# MCU.net
KiCad netlist of a schematic drawn in Altium Designer
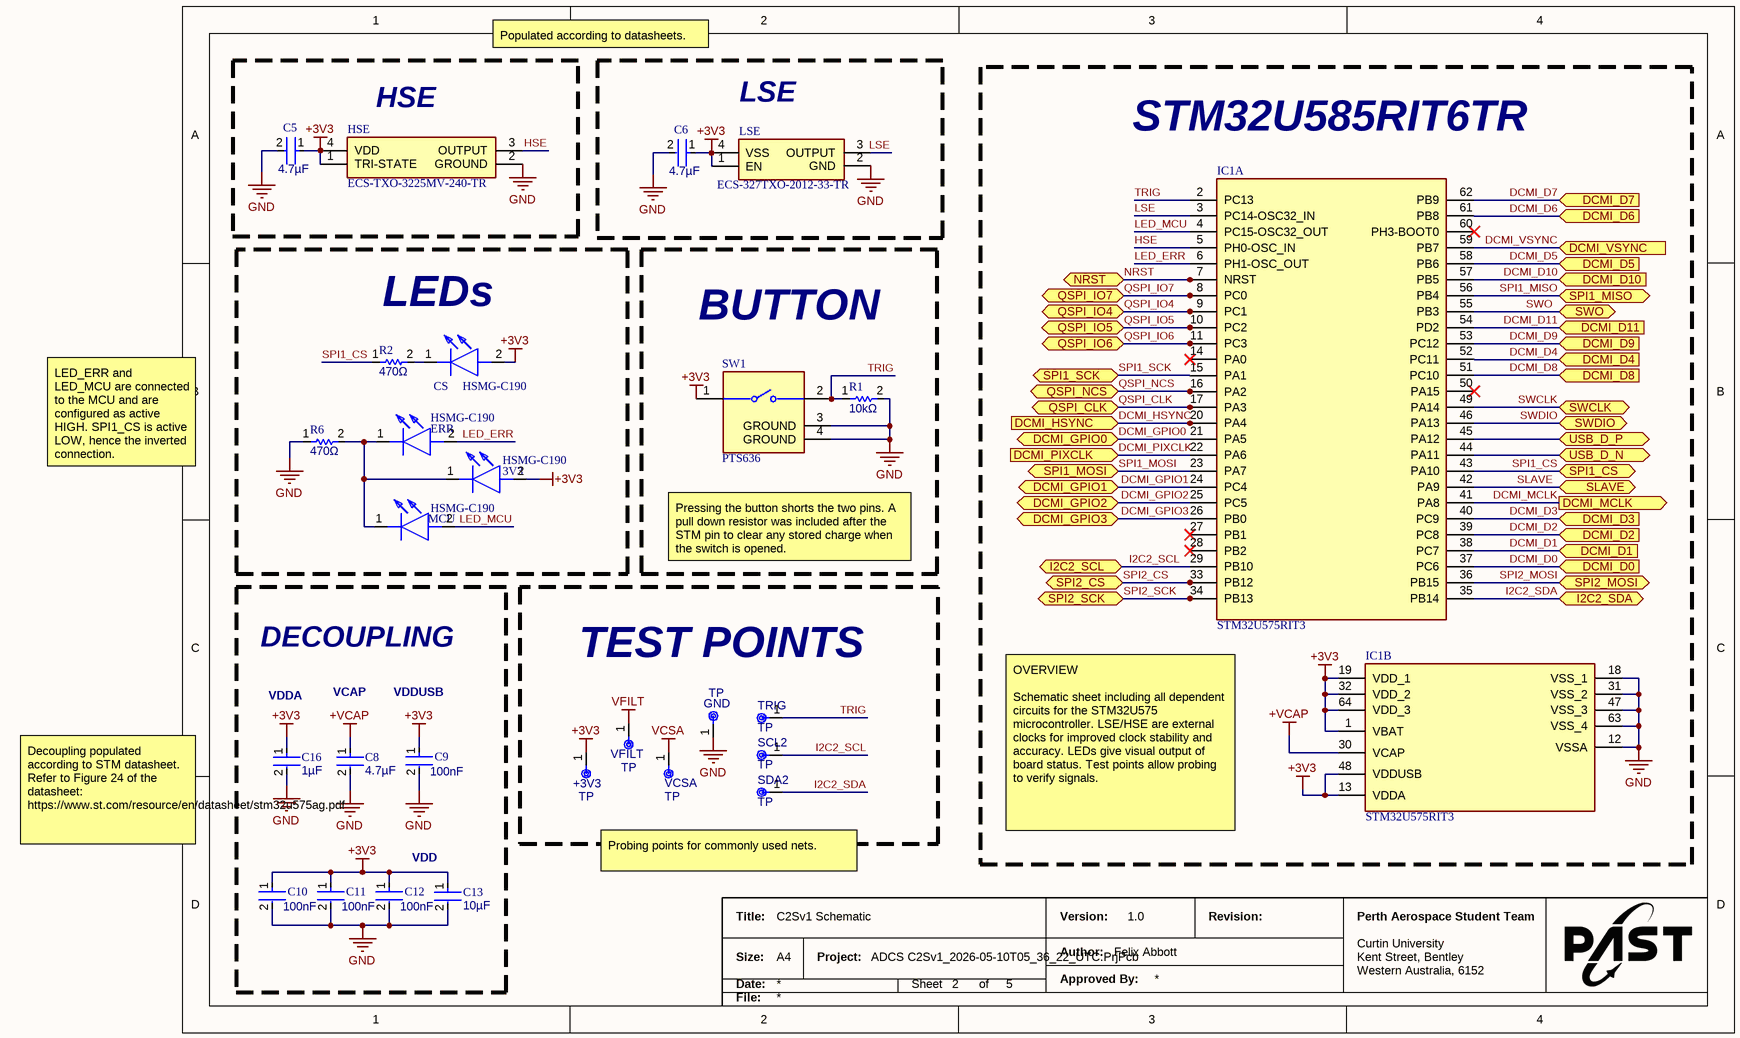
[diagram p0: MCU.SchDoc]

(export (version "E")
  (design (tool "Eeschema 10.0.6"))
  (components
    (comp (ref "+3V3")
      (value "TP")
      (footprint "TP06R")
      (description "test point")
      (fields (field (name "AUTHOR") "Raphael Ho"))
      (libsource (lib "Perth Aerospace Student Team") (part "CMP-001-0001-4"))
    )
    (comp (ref "3V3")
      (value "HSMG-C190")
      (footprint "LEDC1608X90N")
      (description "LED")
      (fields (field (name "MOUSER PART NUMBER") "630-HSMG-C190"))
      (libsource (lib "Perth Aerospace Student Team") (part "HSMG-C190"))
    )
    (comp (ref "C5")
      (value "4.7µF")
      (footprint "FP-GRT188-0_2-IPC_B")
      (fields
        (field (name "TOLERANCE") "10%")
        (field (name "Comment") "GRT188C81E475KE13J")
        (field (name "ADDED BY") "Felix")
      )
      (libsource (lib "Perth Aerospace Student Team") (part "02cd4be3c70576c341d710602a673aa"))
    )
    (comp (ref "C6")
      (value "4.7µF")
      (footprint "FP-GRT188-0_2-IPC_B")
      (fields
        (field (name "TOLERANCE") "10%")
        (field (name "Comment") "GRT188C81E475KE13J")
        (field (name "ADDED BY") "Felix")
      )
      (libsource (lib "Perth Aerospace Student Team") (part "02cd4be3c70576c341d710602a673aa"))
    )
    (comp (ref "C8")
      (value "4.7µF")
      (footprint "FP-GRT188-0_2-IPC_B")
      (fields
        (field (name "TOLERANCE") "10%")
        (field (name "Comment") "GRT188C81E475KE13J")
        (field (name "ADDED BY") "Felix")
      )
      (libsource (lib "Perth Aerospace Student Team") (part "02cd4be3c70576c341d710602a673aa"))
    )
    (comp (ref "C9")
      (value "100nF")
      (footprint "FP-GCM188-0_1-IPC_B")
      (description "Cap Ceramic 0.1uF 50V X8L 20% Pad SMD 0603 150C Automotive T/R")
      (fields
        (field (name "TOLERANCE") "20%")
        (field (name "Comment") "GCM188L81H104MA57D")
        (field (name "ADDED BY") "Felix")
      )
      (libsource (lib "Perth Aerospace Student Team") (part "02cd4be3c70576c341d710602a673aa"))
    )
    (comp (ref "C10")
      (value "100nF")
      (footprint "FP-GCM188-0_1-IPC_B")
      (description "Cap Ceramic 0.1uF 50V X8L 20% Pad SMD 0603 150C Automotive T/R")
      (fields
        (field (name "TOLERANCE") "20%")
        (field (name "Comment") "GCM188L81H104MA57D")
        (field (name "ADDED BY") "Felix")
      )
      (libsource (lib "Perth Aerospace Student Team") (part "02cd4be3c70576c341d710602a673aa"))
    )
    (comp (ref "C11")
      (value "100nF")
      (footprint "FP-GCM188-0_1-IPC_B")
      (description "Cap Ceramic 0.1uF 50V X8L 20% Pad SMD 0603 150C Automotive T/R")
      (fields
        (field (name "TOLERANCE") "20%")
        (field (name "Comment") "GCM188L81H104MA57D")
        (field (name "ADDED BY") "Felix")
      )
      (libsource (lib "Perth Aerospace Student Team") (part "02cd4be3c70576c341d710602a673aa"))
    )
    (comp (ref "C12")
      (value "100nF")
      (footprint "FP-GCM188-0_1-IPC_B")
      (description "Cap Ceramic 0.1uF 50V X8L 20% Pad SMD 0603 150C Automotive T/R")
      (fields
        (field (name "TOLERANCE") "20%")
        (field (name "Comment") "GCM188L81H104MA57D")
        (field (name "ADDED BY") "Felix")
      )
      (libsource (lib "Perth Aerospace Student Team") (part "02cd4be3c70576c341d710602a673aa"))
    )
    (comp (ref "C13")
      (value "10µF")
      (footprint "FP-GCM188-0_2-IPC_B")
      (description "6.3V 10uF X7T ±20% 0603 Multilayer Ceramic Capacitors MLCC - SMD/SMT ROHS")
      (fields
        (field (name "TOLERANCE") "20%")
        (field (name "Comment") "GCM188D70J106ME36D")
        (field (name "ADDED BY") "Felix")
      )
      (libsource (lib "Perth Aerospace Student Team") (part "11868f565c42a9108669ba33697ecf6"))
    )
    (comp (ref "C16")
      (value "1µF")
      (footprint "FP-GCM188-0_1-IPC_B")
      (description "16V 1uF X7R ±10% 0603 Multilayer Ceramic Capacitors MLCC - SMD/SMT ROHS")
      (fields
        (field (name "TOLERANCE") "10%")
        (field (name "Comment") "GCM188R71C105KA64J")
        (field (name "ADDED BY") "Felix")
      )
      (libsource (lib "Perth Aerospace Student Team") (part "02cd4be3c70576c341d710602a673aa"))
    )
    (comp (ref "CS")
      (value "HSMG-C190")
      (footprint "LEDC1608X90N")
      (description "LED")
      (fields (field (name "MOUSER PART NUMBER") "630-HSMG-C190"))
      (libsource (lib "Perth Aerospace Student Team") (part "HSMG-C190"))
    )
    (comp (ref "ERR")
      (value "HSMG-C190")
      (footprint "LEDC1608X90N")
      (description "LED")
      (fields (field (name "MOUSER PART NUMBER") "630-HSMG-C190"))
      (libsource (lib "Perth Aerospace Student Team") (part "HSMG-C190"))
    )
    (comp (ref "GND")
      (value "TP")
      (footprint "TP06R")
      (description "test point")
      (fields (field (name "AUTHOR") "Raphael Ho"))
      (libsource (lib "Perth Aerospace Student Team") (part "CMP-001-0001-4"))
    )
    (comp (ref "HSE")
      (value "ECS-TXO-3225MV-240-TR")
      (footprint "ECSTXO3225MV240TR")
      (description "Crystal or Oscillator")
      (fields (field (name "MOUSER PART NUMBER") "520-TXO-3225MV-240-T") (field (name "IMPORTED BY") "Felix"))
      (libsource (lib "Perth Aerospace Student Team") (part "ECS-TXO-3225MV-240-TR"))
    )
    (comp (ref "IC1")
      (value "STM32U575RIT3")
      (footprint "QFP50P1200X1200X160-64N")
      (description "Ultra-low-power Arm Cortex-M33 32-bit MCU+TrustZone+FPU")
      (fields (field (name "ADDED BY") "Felix Abbott"))
      (libsource (lib "Perth Aerospace Student Team") (part "STM32U575RIT3"))
    )
    (comp (ref "LSE")
      (value "ECS-327TXO-2012-33-TR")
      (footprint "ECS327TXO201233TR")
      (description "Crystal or Oscillator")
      (fields (field (name "MOUSER PART NUMBER") "520-327TXO-2012-33TR") (field (name "ADDED BY") "Felix"))
      (libsource (lib "Perth Aerospace Student Team") (part "ECS-327TXO-2012-33-TR"))
    )
    (comp (ref "MCU")
      (value "HSMG-C190")
      (footprint "LEDC1608X90N")
      (description "LED")
      (fields (field (name "MOUSER PART NUMBER") "630-HSMG-C190"))
      (libsource (lib "Perth Aerospace Student Team") (part "HSMG-C190"))
    )
    (comp (ref "R1")
      (value "10kΩ")
      (footprint "FP-CRCW0603-e3-IPC_C")
      (description "Resistor")
      (fields
        (field (name "TOLERANCE") "1%")
        (field (name "Comment") "CRCW060310K0FKED")
        (field (name "ADDED BY") "Felix")
      )
      (libsource (lib "") (part "1029c3af85768c4190bb7ad29bc67b5_1"))
    )
    (comp (ref "R2")
      (value "470Ω")
      (footprint "FP-CRCW0603-e3-IPC_C")
      (description "Resistor")
      (fields
        (field (name "TOLERANCE") "1%")
        (field (name "Comment") "CRCW0603470RFKEC")
        (field (name "ADDED BY") "Felix")
      )
      (libsource (lib "Perth Aerospace Student Team") (part "1029c3af85768c4190bb7ad29bc67b5"))
    )
    (comp (ref "R6")
      (value "470Ω")
      (footprint "FP-CRCW0603-e3-IPC_C")
      (description "Resistor")
      (fields
        (field (name "TOLERANCE") "1%")
        (field (name "Comment") "CRCW0603470RFKEC")
        (field (name "ADDED BY") "Felix")
      )
      (libsource (lib "Perth Aerospace Student Team") (part "1029c3af85768c4190bb7ad29bc67b5"))
    )
    (comp (ref "SCL2")
      (value "TP")
      (footprint "TP06R")
      (description "test point")
      (fields (field (name "AUTHOR") "Raphael Ho"))
      (libsource (lib "Perth Aerospace Student Team") (part "CMP-001-0001-4"))
    )
    (comp (ref "SDA2")
      (value "TP")
      (footprint "TP06R")
      (description "test point")
      (fields (field (name "AUTHOR") "Raphael Ho"))
      (libsource (lib "Perth Aerospace Student Team") (part "CMP-001-0001-4"))
    )
    (comp (ref "SW1")
      (value "PTS636")
      (footprint "FP-PTS636_SKG25_SMTR_LFS-MFG")
      (description "Tactile Switch")
      (fields (field (name "ADDED BY") "Felix A"))
      (libsource (lib "Perth Aerospace Student Team") (part "bdfe703aeb3461bf7c331fe9d798369"))
    )
    (comp (ref "TRIG")
      (value "TP")
      (footprint "TP06R")
      (description "test point")
      (fields (field (name "AUTHOR") "Raphael Ho"))
      (libsource (lib "Perth Aerospace Student Team") (part "CMP-001-0001-4"))
    )
    (comp (ref "VCSA")
      (value "TP")
      (footprint "TP06R")
      (description "test point")
      (fields (field (name "AUTHOR") "Raphael Ho"))
      (libsource (lib "Perth Aerospace Student Team") (part "CMP-001-0001-4"))
    )
    (comp (ref "VFILT")
      (value "TP")
      (footprint "TP06R")
      (description "test point")
      (fields (field (name "AUTHOR") "Raphael Ho"))
      (libsource (lib "Perth Aerospace Student Team") (part "CMP-001-0001-4"))
    )
  )
  (nets
    (net (code "1") (name "+3V3") (class "Default")
      (node (ref "+3V3") (pin "1") (pinfunction "TP_1") (pintype "passive"))
      (node (ref "3V3") (pin "2") (pinfunction "A_2") (pintype "passive"))
      (node (ref "C10") (pin "1") (pinfunction "1_1") (pintype "passive"))
      (node (ref "C11") (pin "1") (pinfunction "1_1") (pintype "passive"))
      (node (ref "C12") (pin "1") (pinfunction "1_1") (pintype "passive"))
      (node (ref "C13") (pin "1") (pinfunction "1_1") (pintype "passive"))
      (node (ref "C16") (pin "1") (pinfunction "1_1") (pintype "passive"))
      (node (ref "C5") (pin "1") (pinfunction "1_1") (pintype "passive"))
      (node (ref "C6") (pin "1") (pinfunction "1_1") (pintype "passive"))
      (node (ref "C9") (pin "1") (pinfunction "1_1") (pintype "passive"))
      (node (ref "CS") (pin "2") (pinfunction "A_2") (pintype "passive"))
      (node (ref "HSE") (pin "1") (pinfunction "TRI-STATE_1") (pintype "passive"))
      (node (ref "HSE") (pin "4") (pinfunction "VDD_4") (pintype "passive"))
      (node (ref "IC1") (pin "1") (pinfunction "VBAT_1") (pintype "passive"))
      (node (ref "IC1") (pin "13") (pinfunction "VDDA_13") (pintype "passive"))
      (node (ref "IC1") (pin "19") (pinfunction "VDD_1_19") (pintype "passive"))
      (node (ref "IC1") (pin "32") (pinfunction "VDD_2_32") (pintype "passive"))
      (node (ref "IC1") (pin "48") (pinfunction "VDDUSB_48") (pintype "passive"))
      (node (ref "IC1") (pin "64") (pinfunction "VDD_3_64") (pintype "passive"))
      (node (ref "LSE") (pin "1") (pinfunction "EN_1") (pintype "passive"))
      (node (ref "LSE") (pin "4") (pinfunction "VSS_4") (pintype "passive"))
      (node (ref "SW1") (pin "1") (pinfunction "1_1") (pintype "passive"))
    )
    (net (code "2") (name "+VCAP") (class "Default")
      (node (ref "C8") (pin "1") (pinfunction "1_1") (pintype "passive"))
      (node (ref "IC1") (pin "30") (pinfunction "VCAP_30") (pintype "passive"))
    )
    (net (code "3") (name "/DCMI_D0") (class "Default")
      (node (ref "IC1") (pin "37") (pinfunction "PC6_37") (pintype "passive"))
    )
    (net (code "4") (name "/DCMI_D1") (class "Default")
      (node (ref "IC1") (pin "38") (pinfunction "PC7_38") (pintype "passive"))
    )
    (net (code "5") (name "/DCMI_D2") (class "Default")
      (node (ref "IC1") (pin "39") (pinfunction "PC8_39") (pintype "passive"))
    )
    (net (code "6") (name "/DCMI_D3") (class "Default")
      (node (ref "IC1") (pin "40") (pinfunction "PC9_40") (pintype "passive"))
    )
    (net (code "7") (name "/DCMI_D4") (class "Default")
      (node (ref "IC1") (pin "52") (pinfunction "PC11_52") (pintype "passive"))
    )
    (net (code "8") (name "/DCMI_D5") (class "Default")
      (node (ref "IC1") (pin "58") (pinfunction "PB6_58") (pintype "passive"))
    )
    (net (code "9") (name "/DCMI_D6") (class "Default")
      (node (ref "IC1") (pin "61") (pinfunction "PB8_61") (pintype "passive"))
    )
    (net (code "10") (name "/DCMI_D7") (class "Default")
      (node (ref "IC1") (pin "62") (pinfunction "PB9_62") (pintype "passive"))
    )
    (net (code "11") (name "/DCMI_D8") (class "Default")
      (node (ref "IC1") (pin "51") (pinfunction "PC10_51") (pintype "passive"))
    )
    (net (code "12") (name "/DCMI_D9") (class "Default")
      (node (ref "IC1") (pin "53") (pinfunction "PC12_53") (pintype "passive"))
    )
    (net (code "13") (name "/DCMI_D10") (class "Default")
      (node (ref "IC1") (pin "57") (pinfunction "PB5_57") (pintype "passive"))
    )
    (net (code "14") (name "/DCMI_D11") (class "Default")
      (node (ref "IC1") (pin "54") (pinfunction "PD2_54") (pintype "passive"))
    )
    (net (code "15") (name "/DCMI_GPIO0") (class "Default")
      (node (ref "IC1") (pin "21") (pinfunction "PA5_21") (pintype "passive"))
    )
    (net (code "16") (name "/DCMI_GPIO1") (class "Default")
      (node (ref "IC1") (pin "24") (pinfunction "PC4_24") (pintype "passive"))
    )
    (net (code "17") (name "/DCMI_GPIO2") (class "Default")
      (node (ref "IC1") (pin "25") (pinfunction "PC5_25") (pintype "passive"))
    )
    (net (code "18") (name "/DCMI_GPIO3") (class "Default")
      (node (ref "IC1") (pin "26") (pinfunction "PB0_26") (pintype "passive"))
    )
    (net (code "19") (name "/DCMI_HSYNC") (class "Default")
      (node (ref "IC1") (pin "20") (pinfunction "PA4_20") (pintype "passive"))
    )
    (net (code "20") (name "/DCMI_MCLK") (class "Default")
      (node (ref "IC1") (pin "41") (pinfunction "PA8_41") (pintype "passive"))
    )
    (net (code "21") (name "/DCMI_PIXCLK") (class "Default")
      (node (ref "IC1") (pin "22") (pinfunction "PA6_22") (pintype "passive"))
    )
    (net (code "22") (name "/DCMI_VSYNC") (class "Default")
      (node (ref "IC1") (pin "59") (pinfunction "PB7_59") (pintype "passive"))
    )
    (net (code "23") (name "/HSE") (class "Default")
      (node (ref "HSE") (pin "3") (pinfunction "OUTPUT_3") (pintype "passive"))
      (node (ref "IC1") (pin "5") (pinfunction "PH0-OSC_IN_5") (pintype "passive"))
    )
    (net (code "24") (name "/I2C2_SCL") (class "Default")
      (node (ref "IC1") (pin "29") (pinfunction "PB10_29") (pintype "passive"))
      (node (ref "SCL2") (pin "1") (pinfunction "TP_1") (pintype "passive"))
    )
    (net (code "25") (name "/I2C2_SDA") (class "Default")
      (node (ref "IC1") (pin "35") (pinfunction "PB14_35") (pintype "passive"))
      (node (ref "SDA2") (pin "1") (pinfunction "TP_1") (pintype "passive"))
    )
    (net (code "26") (name "/LED_ERR") (class "Default")
      (node (ref "ERR") (pin "2") (pinfunction "A_2") (pintype "passive"))
      (node (ref "IC1") (pin "6") (pinfunction "PH1-OSC_OUT_6") (pintype "passive"))
    )
    (net (code "27") (name "/LED_MCU") (class "Default")
      (node (ref "IC1") (pin "4") (pinfunction "PC15-OSC32_OUT_4") (pintype "passive"))
      (node (ref "MCU") (pin "2") (pinfunction "A_2") (pintype "passive"))
    )
    (net (code "28") (name "/LSE") (class "Default")
      (node (ref "IC1") (pin "3") (pinfunction "PC14-OSC32_IN_3") (pintype "passive"))
      (node (ref "LSE") (pin "3") (pinfunction "OUTPUT_3") (pintype "passive"))
    )
    (net (code "29") (name "/NRST") (class "Default")
      (node (ref "IC1") (pin "7") (pinfunction "NRST_7") (pintype "passive"))
    )
    (net (code "30") (name "/QSPI_CLK") (class "Default")
      (node (ref "IC1") (pin "17") (pinfunction "PA3_17") (pintype "passive"))
    )
    (net (code "31") (name "/QSPI_IO4") (class "Default")
      (node (ref "IC1") (pin "9") (pinfunction "PC1_9") (pintype "passive"))
    )
    (net (code "32") (name "/QSPI_IO5") (class "Default")
      (node (ref "IC1") (pin "10") (pinfunction "PC2_10") (pintype "passive"))
    )
    (net (code "33") (name "/QSPI_IO6") (class "Default")
      (node (ref "IC1") (pin "11") (pinfunction "PC3_11") (pintype "passive"))
    )
    (net (code "34") (name "/QSPI_IO7") (class "Default")
      (node (ref "IC1") (pin "8") (pinfunction "PC0_8") (pintype "passive"))
    )
    (net (code "35") (name "/QSPI_NCS") (class "Default")
      (node (ref "IC1") (pin "16") (pinfunction "PA2_16") (pintype "passive"))
    )
    (net (code "36") (name "/SLAVE") (class "Default")
      (node (ref "IC1") (pin "42") (pinfunction "PA9_42") (pintype "passive"))
    )
    (net (code "37") (name "/SPI1_CS") (class "Default")
      (node (ref "IC1") (pin "43") (pinfunction "PA10_43") (pintype "passive"))
      (node (ref "R2") (pin "1") (pinfunction "1_1") (pintype "passive"))
    )
    (net (code "38") (name "/SPI1_MISO") (class "Default")
      (node (ref "IC1") (pin "56") (pinfunction "PB4_56") (pintype "passive"))
    )
    (net (code "39") (name "/SPI1_MOSI") (class "Default")
      (node (ref "IC1") (pin "23") (pinfunction "PA7_23") (pintype "passive"))
    )
    (net (code "40") (name "/SPI1_SCK") (class "Default")
      (node (ref "IC1") (pin "15") (pinfunction "PA1_15") (pintype "passive"))
    )
    (net (code "41") (name "/SPI2_CS") (class "Default")
      (node (ref "IC1") (pin "33") (pinfunction "PB12_33") (pintype "passive"))
    )
    (net (code "42") (name "/SPI2_MOSI") (class "Default")
      (node (ref "IC1") (pin "36") (pinfunction "PB15_36") (pintype "passive"))
    )
    (net (code "43") (name "/SPI2_SCK") (class "Default")
      (node (ref "IC1") (pin "34") (pinfunction "PB13_34") (pintype "passive"))
    )
    (net (code "44") (name "/SWCLK") (class "Default")
      (node (ref "IC1") (pin "49") (pinfunction "PA14_49") (pintype "passive"))
    )
    (net (code "45") (name "/SWDIO") (class "Default")
      (node (ref "IC1") (pin "46") (pinfunction "PA13_46") (pintype "passive"))
    )
    (net (code "46") (name "/SWO") (class "Default")
      (node (ref "IC1") (pin "55") (pinfunction "PB3_55") (pintype "passive"))
    )
    (net (code "47") (name "/TRIG") (class "Default")
      (node (ref "IC1") (pin "2") (pinfunction "PC13_2") (pintype "passive"))
      (node (ref "R1") (pin "1") (pinfunction "1_1") (pintype "passive"))
      (node (ref "SW1") (pin "2") (pinfunction "2_2") (pintype "passive"))
      (node (ref "TRIG") (pin "1") (pinfunction "TP_1") (pintype "passive"))
    )
    (net (code "48") (name "/USB_D_N") (class "Default")
      (node (ref "IC1") (pin "44") (pinfunction "PA11_44") (pintype "passive"))
    )
    (net (code "49") (name "/USB_D_P") (class "Default")
      (node (ref "IC1") (pin "45") (pinfunction "PA12_45") (pintype "passive"))
    )
    (net (code "50") (name "GND") (class "Default")
      (node (ref "C10") (pin "2") (pinfunction "2_2") (pintype "passive"))
      (node (ref "C11") (pin "2") (pinfunction "2_2") (pintype "passive"))
      (node (ref "C12") (pin "2") (pinfunction "2_2") (pintype "passive"))
      (node (ref "C13") (pin "2") (pinfunction "2_2") (pintype "passive"))
      (node (ref "C16") (pin "2") (pinfunction "2_2") (pintype "passive"))
      (node (ref "C5") (pin "2") (pinfunction "2_2") (pintype "passive"))
      (node (ref "C6") (pin "2") (pinfunction "2_2") (pintype "passive"))
      (node (ref "C8") (pin "2") (pinfunction "2_2") (pintype "passive"))
      (node (ref "C9") (pin "2") (pinfunction "2_2") (pintype "passive"))
      (node (ref "GND") (pin "1") (pinfunction "TP_1") (pintype "passive"))
      (node (ref "HSE") (pin "2") (pinfunction "GROUND_2") (pintype "passive"))
      (node (ref "IC1") (pin "12") (pinfunction "VSSA_12") (pintype "passive"))
      (node (ref "IC1") (pin "18") (pinfunction "VSS_1_18") (pintype "passive"))
      (node (ref "IC1") (pin "31") (pinfunction "VSS_2_31") (pintype "passive"))
      (node (ref "IC1") (pin "47") (pinfunction "VSS_3_47") (pintype "passive"))
      (node (ref "IC1") (pin "63") (pinfunction "VSS_4_63") (pintype "passive"))
      (node (ref "LSE") (pin "2") (pinfunction "GND_2") (pintype "passive"))
      (node (ref "R1") (pin "2") (pinfunction "2_2") (pintype "passive"))
      (node (ref "R6") (pin "1") (pinfunction "1_1") (pintype "passive"))
      (node (ref "SW1") (pin "3") (pinfunction "GROUND_3") (pintype "power_in"))
      (node (ref "SW1") (pin "4") (pinfunction "GROUND_4") (pintype "power_in"))
    )
    (net (code "51") (name "Net-(3V3-K)") (class "Default")
      (node (ref "3V3") (pin "1") (pinfunction "K_1") (pintype "passive"))
      (node (ref "ERR") (pin "1") (pinfunction "K_1") (pintype "passive"))
      (node (ref "MCU") (pin "1") (pinfunction "K_1") (pintype "passive"))
      (node (ref "R6") (pin "2") (pinfunction "2_2") (pintype "passive"))
    )
    (net (code "52") (name "Net-(CS-K)") (class "Default")
      (node (ref "CS") (pin "1") (pinfunction "K_1") (pintype "passive"))
      (node (ref "R2") (pin "2") (pinfunction "2_2") (pintype "passive"))
    )
    (net (code "53") (name "VCSA") (class "Default")
      (node (ref "VCSA") (pin "1") (pinfunction "TP_1") (pintype "passive"))
    )
    (net (code "54") (name "VFILT") (class "Default")
      (node (ref "VFILT") (pin "1") (pinfunction "TP_1") (pintype "passive"))
    )
    (net (code "55") (name "unconnected-(IC1A-PA0-Pad14)") (class "Default")
      (node (ref "IC1") (pin "14") (pinfunction "PA0_14") (pintype "passive+no_connect"))
    )
    (net (code "56") (name "unconnected-(IC1A-PA15-Pad50)") (class "Default")
      (node (ref "IC1") (pin "50") (pinfunction "PA15_50") (pintype "passive+no_connect"))
    )
    (net (code "57") (name "unconnected-(IC1A-PB1-Pad27)") (class "Default")
      (node (ref "IC1") (pin "27") (pinfunction "PB1_27") (pintype "passive+no_connect"))
    )
    (net (code "58") (name "unconnected-(IC1A-PB2-Pad28)") (class "Default")
      (node (ref "IC1") (pin "28") (pinfunction "PB2_28") (pintype "passive+no_connect"))
    )
    (net (code "59") (name "unconnected-(IC1A-PH3-BOOT0-Pad60)") (class "Default")
      (node (ref "IC1") (pin "60") (pinfunction "PH3-BOOT0_60") (pintype "passive+no_connect"))
    )
  )
)
